# fonte1.net
KiCad netlist of a schematic drawn in EAGLE
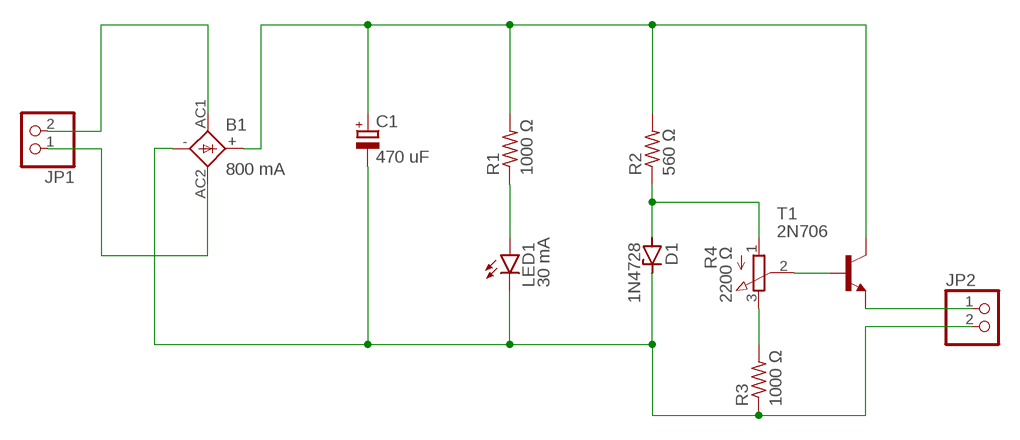
[diagram p0: schematic, sheet 1]

(export (version "E")
  (design (tool "Eeschema 10.0.6"))
  (components
    (comp (ref "B1")
      (value "800 mA")
      (footprint "eagle-import:1KAB")
      (libsource (lib "eagle-import") (part "1KAB"))
    )
    (comp (ref "C1")
      (value "470 uF")
      (footprint "eagle-import:E3,5-10")
      (libsource (lib "eagle-import") (part "CPOL-EUE3.5-10"))
    )
    (comp (ref "D1")
      (value "1N4728")
      (footprint "eagle-import:DO41Z10")
      (libsource (lib "eagle-import") (part "1N4728"))
    )
    (comp (ref "JP1")
      (value "PINHD-1X2")
      (footprint "eagle-import:1X02")
      (libsource (lib "eagle-import") (part "PINHD-1X2"))
    )
    (comp (ref "JP2")
      (value "PINHD-1X2")
      (footprint "eagle-import:1X02")
      (libsource (lib "eagle-import") (part "PINHD-1X2"))
    )
    (comp (ref "LED1")
      (value "30 mA")
      (footprint "eagle-import:LED5MM")
      (libsource (lib "eagle-import") (part "LED5MM"))
    )
    (comp (ref "R1")
      (value "1000 Ω")
      (footprint "eagle-import:0309_12")
      (libsource (lib "eagle-import") (part "R-US_0309/12"))
    )
    (comp (ref "R2")
      (value "560 Ω")
      (footprint "eagle-import:0309_12")
      (libsource (lib "eagle-import") (part "R-US_0309/12"))
    )
    (comp (ref "R3")
      (value "1000 Ω")
      (footprint "eagle-import:0309_12")
      (libsource (lib "eagle-import") (part "R-US_0309/12"))
    )
    (comp (ref "R4")
      (value "2200 Ω")
      (footprint "eagle-import:3RP_1610N")
      (libsource (lib "eagle-import") (part "3RP/1610N"))
    )
    (comp (ref "T1")
      (value "2N706")
      (footprint "eagle-import:TO18")
      (libsource (lib "eagle-import") (part "2N706"))
    )
  )
  (nets
    (net (code "1") (name "Net-(B1-PadAC1)") (class "Default")
      (node (ref "B1") (pin "AC1") (pinfunction "AC1_AC1") (pintype "passive"))
      (node (ref "JP1") (pin "2") (pinfunction "2_2") (pintype "passive"))
    )
    (net (code "2") (name "Net-(B1-PadAC2)") (class "Default")
      (node (ref "B1") (pin "AC2") (pinfunction "AC2_AC2") (pintype "passive"))
      (node (ref "JP1") (pin "1") (pinfunction "1_1") (pintype "passive"))
    )
    (net (code "3") (name "Net-(LED1-C)") (class "Default")
      (node (ref "B1") (pin "-") (pinfunction "-_-") (pintype "passive"))
      (node (ref "C1") (pin "-") (pinfunction "-_-") (pintype "passive"))
      (node (ref "D1") (pin "C") (pinfunction "C_C") (pintype "passive"))
      (node (ref "JP2") (pin "2") (pinfunction "2_2") (pintype "passive"))
      (node (ref "LED1") (pin "K") (pinfunction "C_K") (pintype "passive"))
      (node (ref "R3") (pin "1") (pinfunction "1_1") (pintype "passive"))
    )
    (net (code "4") (name "Net-(LED1-PadA)") (class "Default")
      (node (ref "LED1") (pin "A") (pinfunction "A_A") (pintype "passive"))
      (node (ref "R1") (pin "1") (pinfunction "1_1") (pintype "passive"))
    )
    (net (code "5") (name "Net-(R4-A)") (class "Default")
      (node (ref "D1") (pin "A") (pinfunction "A_A") (pintype "passive"))
      (node (ref "R2") (pin "1") (pinfunction "1_1") (pintype "passive"))
      (node (ref "R4") (pin "1") (pinfunction "A_1") (pintype "passive"))
    )
    (net (code "6") (name "Net-(R4-E)") (class "Default")
      (node (ref "R3") (pin "2") (pinfunction "2_2") (pintype "passive"))
      (node (ref "R4") (pin "3") (pinfunction "E_3") (pintype "passive"))
    )
    (net (code "7") (name "Net-(R4-S)") (class "Default")
      (node (ref "R4") (pin "2") (pinfunction "S_2") (pintype "passive"))
      (node (ref "T1") (pin "2") (pinfunction "B_2") (pintype "passive"))
    )
    (net (code "8") (name "Net-(T1-C)") (class "Default")
      (node (ref "B1") (pin "+") (pinfunction "+_+") (pintype "passive"))
      (node (ref "C1") (pin "+") (pinfunction "+_+") (pintype "passive"))
      (node (ref "R1") (pin "2") (pinfunction "2_2") (pintype "passive"))
      (node (ref "R2") (pin "2") (pinfunction "2_2") (pintype "passive"))
      (node (ref "T1") (pin "3") (pinfunction "C_3") (pintype "passive"))
    )
    (net (code "9") (name "Net-(T1-E)") (class "Default")
      (node (ref "JP2") (pin "1") (pinfunction "1_1") (pintype "passive"))
      (node (ref "T1") (pin "1") (pinfunction "E_1") (pintype "passive"))
    )
  )
)
